# Low-Side_Driver.net
KiCad netlist of a schematic drawn in Altium Designer
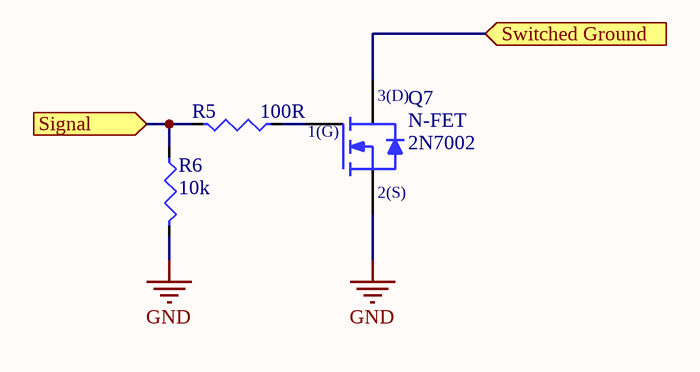
[diagram p0: Low-Side Driver.SchDoc]

(export (version "E")
  (design (tool "Eeschema 10.0.6"))
  (components
    (comp (ref "Q7")
      (value "N-FET")
      (footprint "SOT23 - 3 pin")
      (description "N Channel MOSFET")
      (fields
        (field (name "QUICKVALUE") "2N7002")
        (field (name "MANUFACTURER") "NXP Semiconductors")
        (field (name "MANUFACTURER PART NUMBER") "2N7002,215")
      )
      (libsource (lib "Integrated Component Library") (part "N Channel MOSFET"))
    )
    (comp (ref "R5")
      (value "2k 1206 5%")
      (footprint "Resistor - 1206")
      (description "Resistor")
      (fields
        (field (name "MANUFACTURER") "Yageo")
        (field (name "MANUFACTURER PART NUMBER") "RC1206FR-07100RL")
        (field (name "RESISTANCE (OHMS)") "100R")
      )
      (libsource (lib "Integrated Component Library") (part "2k 1206 5%"))
    )
    (comp (ref "R6")
      (value "~")
      (footprint "Resistor - 1206")
      (description "Resistor")
      (fields
        (field (name "MANUFACTURER") "Vishay Dale")
        (field (name "MANUFACTURER PART NUMBER") "CRCW120610K0FKEA")
        (field (name "RESISTANCE (OHMS)") "10k")
      )
      (libsource (lib "Integrated Component Library") (part "10k 1206 1%"))
    )
  )
  (nets
    (net (code "1") (name "/Signal") (class "Default")
      (node (ref "R5") (pin "1") (pinfunction "1_1") (pintype "passive"))
      (node (ref "R6") (pin "1") (pinfunction "1_1") (pintype "passive"))
    )
    (net (code "2") (name "/Switched Ground") (class "Default")
      (node (ref "Q7") (pin "3") (pinfunction "Drain_3") (pintype "passive"))
    )
    (net (code "3") (name "GND") (class "Default")
      (node (ref "Q7") (pin "2") (pinfunction "Source_2") (pintype "passive"))
      (node (ref "R6") (pin "2") (pinfunction "2_2") (pintype "passive"))
    )
    (net (code "4") (name "Net-(Q7-Gate)") (class "Default")
      (node (ref "Q7") (pin "1") (pinfunction "Gate_1") (pintype "passive"))
      (node (ref "R5") (pin "2") (pinfunction "2_2") (pintype "passive"))
    )
  )
)
